# DDS_rev01.net
KiCad netlist of a schematic drawn in EAGLE
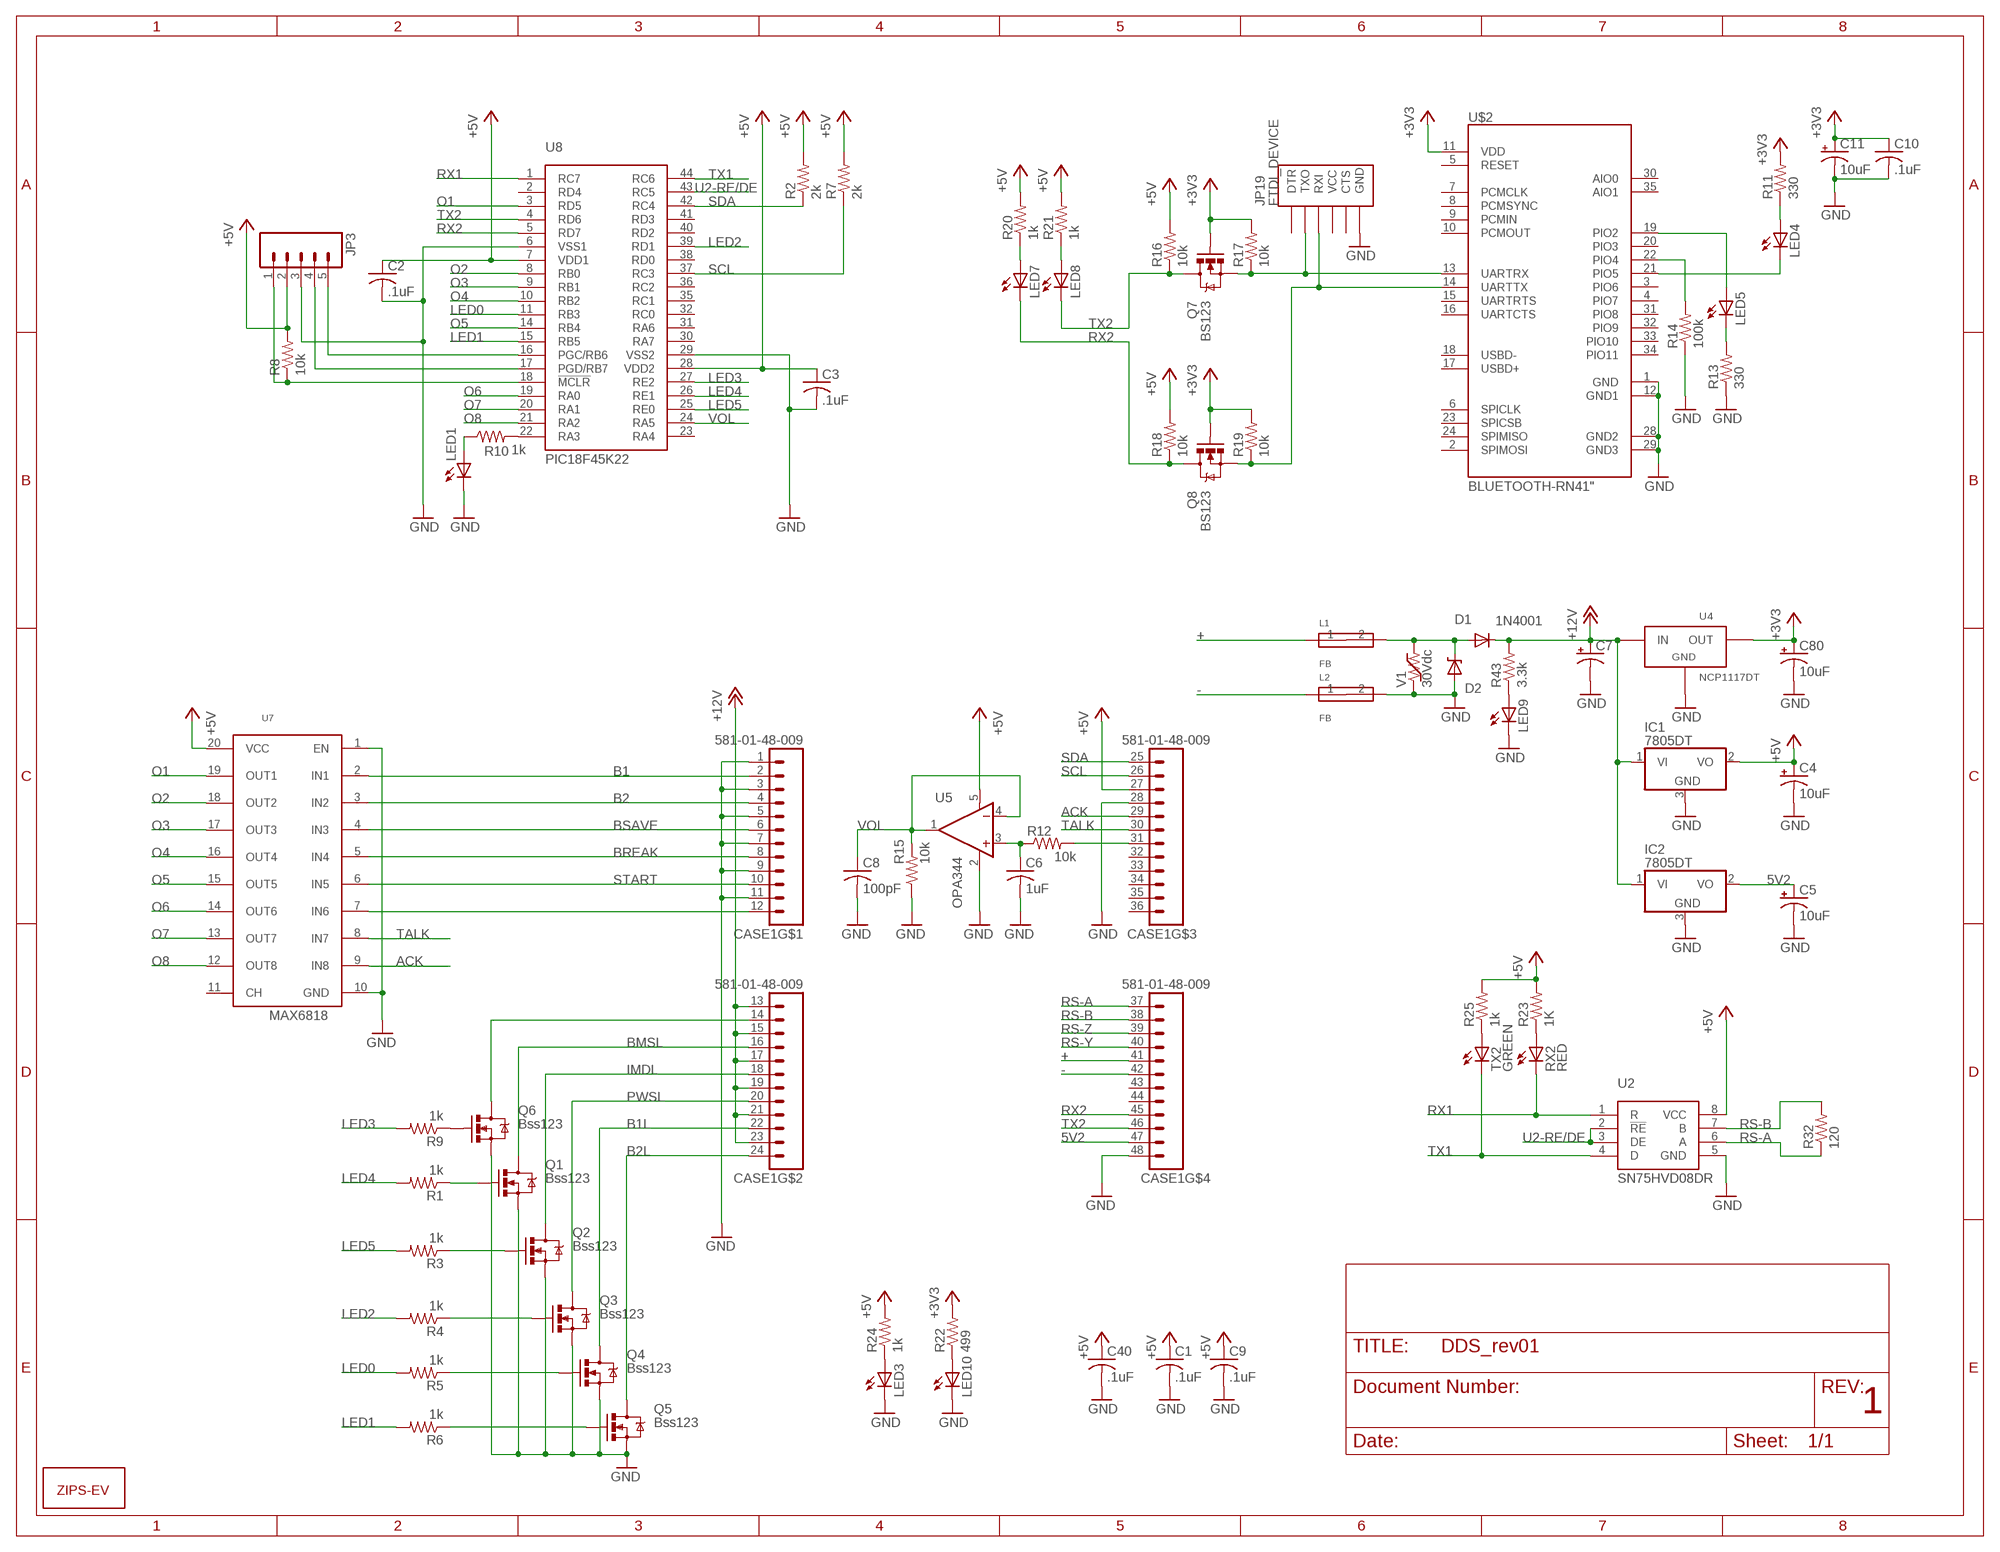
[diagram p0: schematic, sheet 1]

(export (version "E")
  (design (tool "Eeschema 10.0.6"))
  (components
    (comp (ref "C1")
      (value ".1uF")
      (footprint "eagle-import:C0805")
      (libsource (lib "eagle-import") (part "C-USC0805"))
    )
    (comp (ref "C2")
      (value ".1uF")
      (footprint "eagle-import:C0805")
      (libsource (lib "eagle-import") (part "C-USC0805"))
    )
    (comp (ref "C3")
      (value ".1uF")
      (footprint "eagle-import:C0805")
      (libsource (lib "eagle-import") (part "C-USC0805"))
    )
    (comp (ref "C4")
      (value "10uF")
      (footprint "eagle-import:POLC1206")
      (libsource (lib "eagle-import") (part "POLCAP"))
    )
    (comp (ref "C5")
      (value "10uF")
      (footprint "eagle-import:POLC1206")
      (libsource (lib "eagle-import") (part "POLCAP"))
    )
    (comp (ref "C6")
      (value "1uF")
      (footprint "eagle-import:C0805")
      (libsource (lib "eagle-import") (part "C-USC0805"))
    )
    (comp (ref "C7")
      (value "CAP_POL7343")
      (footprint "eagle-import:EIA7343")
      (libsource (lib "eagle-import") (part "CAP_POL7343"))
    )
    (comp (ref "C8")
      (value "100pF")
      (footprint "eagle-import:C0805")
      (libsource (lib "eagle-import") (part "C-USC0805"))
    )
    (comp (ref "C9")
      (value ".1uF")
      (footprint "eagle-import:C0805")
      (libsource (lib "eagle-import") (part "C-USC0805"))
    )
    (comp (ref "C10")
      (value ".1uF")
      (footprint "eagle-import:C0805")
      (libsource (lib "eagle-import") (part "C-USC0805"))
    )
    (comp (ref "C11")
      (value "10uF")
      (footprint "eagle-import:POLC1206")
      (libsource (lib "eagle-import") (part "POLCAP"))
    )
    (comp (ref "C40")
      (value ".1uF")
      (footprint "eagle-import:C0805")
      (libsource (lib "eagle-import") (part "C-USC0805"))
    )
    (comp (ref "C80")
      (value "10uF")
      (footprint "eagle-import:POLC1206")
      (libsource (lib "eagle-import") (part "POLCAP"))
    )
    (comp (ref "CASE1")
      (value "581-01-48-009")
      (footprint "eagle-import:581-01-48-009")
      (libsource (lib "eagle-import") (part "581-01-48-009"))
    )
    (comp (ref "D1")
      (value "1N4001")
      (footprint "eagle-import:SOD123")
      (libsource (lib "eagle-import") (part "DIODE-SOD123"))
    )
    (comp (ref "D2")
      (value "MM5Z30")
      (footprint "eagle-import:SOD-523F")
      (libsource (lib "eagle-import") (part "MM5Z30"))
    )
    (comp (ref "IC1")
      (value "7805DT")
      (footprint "eagle-import:TO252")
      (libsource (lib "eagle-import") (part "78DT05"))
    )
    (comp (ref "IC2")
      (value "7805DT")
      (footprint "eagle-import:TO252")
      (libsource (lib "eagle-import") (part "78DT05"))
    )
    (comp (ref "JP3")
      (value "M05LOCK_LONGPADS")
      (footprint "eagle-import:1X05_LOCK_LONGPADS")
      (libsource (lib "eagle-import") (part "M05LOCK_LONGPADS"))
    )
    (comp (ref "JP19")
      (value "FTDI_DEVICE")
      (footprint "eagle-import:FTDI_DEVICE_SIDE")
      (libsource (lib "eagle-import") (part "FTDI_DEVICE"))
    )
    (comp (ref "L1")
      (value "FB")
      (footprint "eagle-import:0603")
      (libsource (lib "eagle-import") (part "FERITEBEAD"))
    )
    (comp (ref "L2")
      (value "FB")
      (footprint "eagle-import:0603")
      (libsource (lib "eagle-import") (part "FERITEBEAD"))
    )
    (comp (ref "LED1")
      (value "LEDCHIP-LED0805")
      (footprint "eagle-import:CHIP-LED0805")
      (libsource (lib "eagle-import") (part "LEDCHIP-LED0805"))
    )
    (comp (ref "LED3")
      (value "LEDCHIP-LED0805")
      (footprint "eagle-import:CHIP-LED0805")
      (libsource (lib "eagle-import") (part "LEDCHIP-LED0805"))
    )
    (comp (ref "LED4")
      (value "LEDCHIP-LED0805")
      (footprint "eagle-import:CHIP-LED0805")
      (libsource (lib "eagle-import") (part "led_LEDCHIP-LED0805"))
    )
    (comp (ref "LED5")
      (value "LEDCHIP-LED0805")
      (footprint "eagle-import:CHIP-LED0805")
      (libsource (lib "eagle-import") (part "led_LEDCHIP-LED0805"))
    )
    (comp (ref "LED7")
      (value "LEDCHIP-LED0805")
      (footprint "eagle-import:CHIP-LED0805")
      (libsource (lib "eagle-import") (part "led_LEDCHIP-LED0805"))
    )
    (comp (ref "LED8")
      (value "LEDCHIP-LED0805")
      (footprint "eagle-import:CHIP-LED0805")
      (libsource (lib "eagle-import") (part "led_LEDCHIP-LED0805"))
    )
    (comp (ref "LED9")
      (value "LEDCHIP-LED0805")
      (footprint "eagle-import:CHIP-LED0805")
      (libsource (lib "eagle-import") (part "LEDCHIP-LED0805"))
    )
    (comp (ref "LED10")
      (value "LEDCHIP-LED0805")
      (footprint "eagle-import:CHIP-LED0805")
      (libsource (lib "eagle-import") (part "LEDCHIP-LED0805"))
    )
    (comp (ref "Q1")
      (value "Bss123")
      (footprint "eagle-import:SOT23")
      (libsource (lib "eagle-import") (part "MOSFET-NCHANNELBSS123LT1G"))
    )
    (comp (ref "Q2")
      (value "Bss123")
      (footprint "eagle-import:SOT23")
      (libsource (lib "eagle-import") (part "MOSFET-NCHANNELBSS123LT1G"))
    )
    (comp (ref "Q3")
      (value "Bss123")
      (footprint "eagle-import:SOT23")
      (libsource (lib "eagle-import") (part "MOSFET-NCHANNELBSS123LT1G"))
    )
    (comp (ref "Q4")
      (value "Bss123")
      (footprint "eagle-import:SOT23")
      (libsource (lib "eagle-import") (part "MOSFET-NCHANNELBSS123LT1G"))
    )
    (comp (ref "Q5")
      (value "Bss123")
      (footprint "eagle-import:SOT23")
      (libsource (lib "eagle-import") (part "MOSFET-NCHANNELBSS123LT1G"))
    )
    (comp (ref "Q6")
      (value "Bss123")
      (footprint "eagle-import:SOT23")
      (libsource (lib "eagle-import") (part "MOSFET-NCHANNELBSS123LT1G"))
    )
    (comp (ref "Q7")
      (value "BS123")
      (footprint "eagle-import:SOT23")
      (libsource (lib "eagle-import") (part "MOSFET-NCHANNELBSS123LT1G"))
    )
    (comp (ref "Q8")
      (value "BS123")
      (footprint "eagle-import:SOT23")
      (libsource (lib "eagle-import") (part "MOSFET-NCHANNELBSS123LT1G"))
    )
    (comp (ref "R1")
      (value "1k")
      (footprint "eagle-import:R0805")
      (libsource (lib "eagle-import") (part "R-US_R0805"))
    )
    (comp (ref "R2")
      (value "2k")
      (footprint "eagle-import:R0805")
      (libsource (lib "eagle-import") (part "R-US_R0805"))
    )
    (comp (ref "R3")
      (value "1k")
      (footprint "eagle-import:R0805")
      (libsource (lib "eagle-import") (part "R-US_R0805"))
    )
    (comp (ref "R4")
      (value "1k")
      (footprint "eagle-import:R0805")
      (libsource (lib "eagle-import") (part "R-US_R0805"))
    )
    (comp (ref "R5")
      (value "1k")
      (footprint "eagle-import:R0805")
      (libsource (lib "eagle-import") (part "R-US_R0805"))
    )
    (comp (ref "R6")
      (value "1k")
      (footprint "eagle-import:R0805")
      (libsource (lib "eagle-import") (part "R-US_R0805"))
    )
    (comp (ref "R7")
      (value "2k")
      (footprint "eagle-import:R0805")
      (libsource (lib "eagle-import") (part "R-US_R0805"))
    )
    (comp (ref "R8")
      (value "10k")
      (footprint "eagle-import:0805")
      (libsource (lib "eagle-import") (part "RESISTOR0805-RES"))
    )
    (comp (ref "R9")
      (value "1k")
      (footprint "eagle-import:R0805")
      (libsource (lib "eagle-import") (part "R-US_R0805"))
    )
    (comp (ref "R10")
      (value "1k")
      (footprint "eagle-import:R0805")
      (libsource (lib "eagle-import") (part "R-US_R0805"))
    )
    (comp (ref "R11")
      (value "330")
      (footprint "eagle-import:0805")
      (libsource (lib "eagle-import") (part "RESISTOR0805-RES"))
    )
    (comp (ref "R12")
      (value "10k")
      (footprint "eagle-import:R0805")
      (libsource (lib "eagle-import") (part "R-US_R0805"))
    )
    (comp (ref "R13")
      (value "330")
      (footprint "eagle-import:0805")
      (libsource (lib "eagle-import") (part "RESISTOR0805-RES"))
    )
    (comp (ref "R14")
      (value "100k")
      (footprint "eagle-import:0805")
      (libsource (lib "eagle-import") (part "RESISTOR0805-RES"))
    )
    (comp (ref "R15")
      (value "10k")
      (footprint "eagle-import:R0805")
      (libsource (lib "eagle-import") (part "R-US_R0805"))
    )
    (comp (ref "R16")
      (value "10k")
      (footprint "eagle-import:0805")
      (libsource (lib "eagle-import") (part "RESISTOR0805-RES"))
    )
    (comp (ref "R17")
      (value "10k")
      (footprint "eagle-import:0805")
      (libsource (lib "eagle-import") (part "RESISTOR0805-RES"))
    )
    (comp (ref "R18")
      (value "10k")
      (footprint "eagle-import:0805")
      (libsource (lib "eagle-import") (part "RESISTOR0805-RES"))
    )
    (comp (ref "R19")
      (value "10k")
      (footprint "eagle-import:0805")
      (libsource (lib "eagle-import") (part "RESISTOR0805-RES"))
    )
    (comp (ref "R20")
      (value "1k")
      (footprint "eagle-import:0805")
      (libsource (lib "eagle-import") (part "RESISTOR0805-RES"))
    )
    (comp (ref "R21")
      (value "1k")
      (footprint "eagle-import:0805")
      (libsource (lib "eagle-import") (part "RESISTOR0805-RES"))
    )
    (comp (ref "R22")
      (value "499")
      (footprint "eagle-import:R0805")
      (libsource (lib "eagle-import") (part "R-US_R0805"))
    )
    (comp (ref "R23")
      (value "1K")
      (footprint "eagle-import:R0805")
      (libsource (lib "eagle-import") (part "R-US_R0805"))
    )
    (comp (ref "R24")
      (value "1k")
      (footprint "eagle-import:R0805")
      (libsource (lib "eagle-import") (part "R-US_R0805"))
    )
    (comp (ref "R25")
      (value "1k")
      (footprint "eagle-import:R0805")
      (libsource (lib "eagle-import") (part "R-US_R0805"))
    )
    (comp (ref "R32")
      (value "120")
      (footprint "eagle-import:R0805")
      (libsource (lib "eagle-import") (part "R-US_R0805"))
    )
    (comp (ref "R43")
      (value "3.3k")
      (footprint "eagle-import:R0805")
      (libsource (lib "eagle-import") (part "R-US_R0805"))
    )
    (comp (ref "RX2")
      (value "RED")
      (footprint "eagle-import:CHIPLED_0805")
      (libsource (lib "eagle-import") (part "LEDCHIPLED_0805"))
    )
    (comp (ref "TX2")
      (value "GREEN")
      (footprint "eagle-import:CHIPLED_0805")
      (libsource (lib "eagle-import") (part "LEDCHIPLED_0805"))
    )
    (comp (ref "U$1")
      (value "LOGO")
      (footprint "eagle-import:L-L")
      (libsource (lib "eagle-import") (part "LOGO"))
    )
    (comp (ref "U$2")
      (value "BLUETOOTH-RN41\"")
      (footprint "eagle-import:RN41")
      (libsource (lib "eagle-import") (part "BLUETOOTH-RN41{dblquote}"))
    )
    (comp (ref "U2")
      (value "SN75HVD08DR")
      (footprint "eagle-import:SO-8")
      (libsource (lib "eagle-import") (part "SN75HVD08DR"))
    )
    (comp (ref "U4")
      (value "NCP1117DT")
      (footprint "eagle-import:DPAK")
      (libsource (lib "eagle-import") (part "NCP1117DT"))
    )
    (comp (ref "U5")
      (value "OPA344")
      (footprint "eagle-import:SOT23-5")
      (libsource (lib "eagle-import") (part "OPA344"))
    )
    (comp (ref "U7")
      (value "MAX6818")
      (footprint "eagle-import:SSOP-20")
      (libsource (lib "eagle-import") (part "MAX6818"))
    )
    (comp (ref "U8")
      (value "PIC18F45K22")
      (footprint "eagle-import:TQFP-44")
      (libsource (lib "eagle-import") (part "PIC18F45K22"))
    )
    (comp (ref "V1")
      (value "30Vdc")
      (footprint "eagle-import:0603")
      (libsource (lib "eagle-import") (part "VAR-RES"))
    )
  )
  (nets
    (net (code "1") (name "+3V3") (class "Default")
      (node (ref "C10") (pin "1") (pinfunction "1_1") (pintype "passive"))
      (node (ref "C11") (pin "1") (pinfunction "+_1") (pintype "passive"))
      (node (ref "C80") (pin "1") (pinfunction "+_1") (pintype "passive"))
      (node (ref "Q7") (pin "1") (pinfunction "G_1") (pintype "passive"))
      (node (ref "Q8") (pin "1") (pinfunction "G_1") (pintype "passive"))
      (node (ref "R11") (pin "2") (pinfunction "2_2") (pintype "passive"))
      (node (ref "R17") (pin "2") (pinfunction "2_2") (pintype "passive"))
      (node (ref "R19") (pin "2") (pinfunction "2_2") (pintype "passive"))
      (node (ref "R22") (pin "2") (pinfunction "2_2") (pintype "passive"))
      (node (ref "U$2") (pin "11") (pinfunction "VDD_11") (pintype "bidirectional"))
      (node (ref "U4") (pin "2") (pinfunction "OUT_2") (pintype "bidirectional"))
    )
    (net (code "2") (name "+5V") (class "Default")
      (node (ref "C1") (pin "1") (pinfunction "1_1") (pintype "passive"))
      (node (ref "C2") (pin "1") (pinfunction "1_1") (pintype "passive"))
      (node (ref "C3") (pin "1") (pinfunction "1_1") (pintype "passive"))
      (node (ref "C4") (pin "1") (pinfunction "+_1") (pintype "passive"))
      (node (ref "C40") (pin "1") (pinfunction "1_1") (pintype "passive"))
      (node (ref "C9") (pin "1") (pinfunction "1_1") (pintype "passive"))
      (node (ref "CASE1") (pin "27") (pinfunction "3_27") (pintype "passive"))
      (node (ref "IC1") (pin "2") (pinfunction "VO_2") (pintype "passive"))
      (node (ref "JP3") (pin "2") (pinfunction "2_2") (pintype "passive"))
      (node (ref "R16") (pin "2") (pinfunction "2_2") (pintype "passive"))
      (node (ref "R18") (pin "2") (pinfunction "2_2") (pintype "passive"))
      (node (ref "R2") (pin "2") (pinfunction "2_2") (pintype "passive"))
      (node (ref "R20") (pin "2") (pinfunction "2_2") (pintype "passive"))
      (node (ref "R21") (pin "2") (pinfunction "2_2") (pintype "passive"))
      (node (ref "R23") (pin "2") (pinfunction "2_2") (pintype "passive"))
      (node (ref "R24") (pin "2") (pinfunction "2_2") (pintype "passive"))
      (node (ref "R25") (pin "2") (pinfunction "2_2") (pintype "passive"))
      (node (ref "R7") (pin "2") (pinfunction "2_2") (pintype "passive"))
      (node (ref "R8") (pin "2") (pinfunction "2_2") (pintype "passive"))
      (node (ref "U2") (pin "8") (pinfunction "VCC_8") (pintype "bidirectional"))
      (node (ref "U5") (pin "5") (pinfunction "V+_5") (pintype "power_in"))
      (node (ref "U7") (pin "20") (pinfunction "VCC_20") (pintype "bidirectional"))
      (node (ref "U8") (pin "28") (pinfunction "VDD2_28") (pintype "bidirectional"))
      (node (ref "U8") (pin "7") (pinfunction "VDD1_7") (pintype "bidirectional"))
    )
    (net (code "3") (name "+12V") (class "Default")
      (node (ref "C7") (pin "A") (pinfunction "+_A") (pintype "passive"))
      (node (ref "CASE1") (pin "13") (pinfunction "1_13") (pintype "passive"))
      (node (ref "CASE1") (pin "15") (pinfunction "3_15") (pintype "passive"))
      (node (ref "CASE1") (pin "17") (pinfunction "5_17") (pintype "passive"))
      (node (ref "CASE1") (pin "19") (pinfunction "7_19") (pintype "passive"))
      (node (ref "CASE1") (pin "21") (pinfunction "9_21") (pintype "passive"))
      (node (ref "CASE1") (pin "23") (pinfunction "11_23") (pintype "passive"))
      (node (ref "D1") (pin "C") (pinfunction "C_C") (pintype "passive"))
      (node (ref "IC1") (pin "1") (pinfunction "VI_1") (pintype "input"))
      (node (ref "IC2") (pin "1") (pinfunction "VI_1") (pintype "input"))
      (node (ref "R43") (pin "2") (pinfunction "2_2") (pintype "passive"))
      (node (ref "U4") (pin "3") (pinfunction "IN_3") (pintype "bidirectional"))
    )
    (net (code "4") (name "/+") (class "Default")
      (node (ref "CASE1") (pin "41") (pinfunction "5_41") (pintype "passive"))
      (node (ref "L1") (pin "1") (pinfunction "P$1_1") (pintype "bidirectional"))
    )
    (net (code "5") (name "/-") (class "Default")
      (node (ref "CASE1") (pin "42") (pinfunction "6_42") (pintype "passive"))
      (node (ref "L2") (pin "1") (pinfunction "P$1_1") (pintype "bidirectional"))
    )
    (net (code "6") (name "/5V2") (class "Default")
      (node (ref "C5") (pin "1") (pinfunction "+_1") (pintype "passive"))
      (node (ref "CASE1") (pin "47") (pinfunction "11_47") (pintype "passive"))
      (node (ref "IC2") (pin "2") (pinfunction "VO_2") (pintype "passive"))
    )
    (net (code "7") (name "/ACK") (class "Default")
      (node (ref "CASE1") (pin "29") (pinfunction "5_29") (pintype "passive"))
      (node (ref "U7") (pin "9") (pinfunction "IN8_9") (pintype "bidirectional"))
    )
    (net (code "8") (name "/B1") (class "Default")
      (node (ref "CASE1") (pin "2") (pinfunction "2_2") (pintype "passive"))
      (node (ref "U7") (pin "2") (pinfunction "IN1_2") (pintype "bidirectional"))
    )
    (net (code "9") (name "/B1L") (class "Default")
      (node (ref "CASE1") (pin "22") (pinfunction "10_22") (pintype "passive"))
      (node (ref "Q4") (pin "3") (pinfunction "D_3") (pintype "passive"))
    )
    (net (code "10") (name "/B2") (class "Default")
      (node (ref "CASE1") (pin "4") (pinfunction "4_4") (pintype "passive"))
      (node (ref "U7") (pin "3") (pinfunction "IN2_3") (pintype "bidirectional"))
    )
    (net (code "11") (name "/B2L") (class "Default")
      (node (ref "CASE1") (pin "24") (pinfunction "12_24") (pintype "passive"))
      (node (ref "Q5") (pin "3") (pinfunction "D_3") (pintype "passive"))
    )
    (net (code "12") (name "/BMSL") (class "Default")
      (node (ref "CASE1") (pin "16") (pinfunction "4_16") (pintype "passive"))
      (node (ref "Q1") (pin "3") (pinfunction "D_3") (pintype "passive"))
    )
    (net (code "13") (name "/BREAK") (class "Default")
      (node (ref "CASE1") (pin "8") (pinfunction "8_8") (pintype "passive"))
      (node (ref "U7") (pin "5") (pinfunction "IN4_5") (pintype "bidirectional"))
    )
    (net (code "14") (name "/BSAVE") (class "Default")
      (node (ref "CASE1") (pin "6") (pinfunction "6_6") (pintype "passive"))
      (node (ref "U7") (pin "4") (pinfunction "IN3_4") (pintype "bidirectional"))
    )
    (net (code "15") (name "/IMDL") (class "Default")
      (node (ref "CASE1") (pin "18") (pinfunction "6_18") (pintype "passive"))
      (node (ref "Q2") (pin "3") (pinfunction "D_3") (pintype "passive"))
    )
    (net (code "16") (name "/LED0") (class "Default")
      (node (ref "R5") (pin "2") (pinfunction "2_2") (pintype "passive"))
      (node (ref "U8") (pin "11") (pinfunction "RB3_11") (pintype "bidirectional"))
    )
    (net (code "17") (name "/LED1") (class "Default")
      (node (ref "R6") (pin "2") (pinfunction "2_2") (pintype "passive"))
      (node (ref "U8") (pin "15") (pinfunction "RB5_15") (pintype "bidirectional"))
    )
    (net (code "18") (name "/LED2") (class "Default")
      (node (ref "R4") (pin "2") (pinfunction "2_2") (pintype "passive"))
      (node (ref "U8") (pin "39") (pinfunction "RD1_39") (pintype "bidirectional"))
    )
    (net (code "19") (name "/LED3") (class "Default")
      (node (ref "R9") (pin "2") (pinfunction "2_2") (pintype "passive"))
      (node (ref "U8") (pin "27") (pinfunction "RE2_27") (pintype "bidirectional"))
    )
    (net (code "20") (name "/LED4") (class "Default")
      (node (ref "R1") (pin "2") (pinfunction "2_2") (pintype "passive"))
      (node (ref "U8") (pin "26") (pinfunction "RE1_26") (pintype "bidirectional"))
    )
    (net (code "21") (name "/LED5") (class "Default")
      (node (ref "R3") (pin "2") (pinfunction "2_2") (pintype "passive"))
      (node (ref "U8") (pin "25") (pinfunction "RE0_25") (pintype "bidirectional"))
    )
    (net (code "22") (name "/O1") (class "Default")
      (node (ref "U7") (pin "19") (pinfunction "OUT1_19") (pintype "bidirectional"))
      (node (ref "U8") (pin "3") (pinfunction "RD5_3") (pintype "bidirectional"))
    )
    (net (code "23") (name "/O2") (class "Default")
      (node (ref "U7") (pin "18") (pinfunction "OUT2_18") (pintype "bidirectional"))
      (node (ref "U8") (pin "8") (pinfunction "RB0_8") (pintype "bidirectional"))
    )
    (net (code "24") (name "/O3") (class "Default")
      (node (ref "U7") (pin "17") (pinfunction "OUT3_17") (pintype "bidirectional"))
      (node (ref "U8") (pin "9") (pinfunction "RB1_9") (pintype "bidirectional"))
    )
    (net (code "25") (name "/O4") (class "Default")
      (node (ref "U7") (pin "16") (pinfunction "OUT4_16") (pintype "bidirectional"))
      (node (ref "U8") (pin "10") (pinfunction "RB2_10") (pintype "bidirectional"))
    )
    (net (code "26") (name "/O5") (class "Default")
      (node (ref "U7") (pin "15") (pinfunction "OUT5_15") (pintype "bidirectional"))
      (node (ref "U8") (pin "14") (pinfunction "RB4_14") (pintype "bidirectional"))
    )
    (net (code "27") (name "/O6") (class "Default")
      (node (ref "U7") (pin "14") (pinfunction "OUT6_14") (pintype "bidirectional"))
      (node (ref "U8") (pin "19") (pinfunction "RA0_19") (pintype "bidirectional"))
    )
    (net (code "28") (name "/O7") (class "Default")
      (node (ref "U7") (pin "13") (pinfunction "OUT7_13") (pintype "bidirectional"))
      (node (ref "U8") (pin "20") (pinfunction "RA1_20") (pintype "bidirectional"))
    )
    (net (code "29") (name "/O8") (class "Default")
      (node (ref "U7") (pin "12") (pinfunction "OUT8_12") (pintype "bidirectional"))
      (node (ref "U8") (pin "21") (pinfunction "RA2_21") (pintype "bidirectional"))
    )
    (net (code "30") (name "/PWSL") (class "Default")
      (node (ref "CASE1") (pin "20") (pinfunction "8_20") (pintype "passive"))
      (node (ref "Q3") (pin "3") (pinfunction "D_3") (pintype "passive"))
    )
    (net (code "31") (name "/RS-A") (class "Default")
      (node (ref "CASE1") (pin "37") (pinfunction "1_37") (pintype "passive"))
      (node (ref "R32") (pin "1") (pinfunction "1_1") (pintype "passive"))
      (node (ref "U2") (pin "6") (pinfunction "A_6") (pintype "bidirectional"))
    )
    (net (code "32") (name "/RS-B") (class "Default")
      (node (ref "CASE1") (pin "38") (pinfunction "2_38") (pintype "passive"))
      (node (ref "R32") (pin "2") (pinfunction "2_2") (pintype "passive"))
      (node (ref "U2") (pin "7") (pinfunction "B_7") (pintype "bidirectional"))
    )
    (net (code "33") (name "/RS-Y") (class "Default")
      (node (ref "CASE1") (pin "40") (pinfunction "4_40") (pintype "passive"))
    )
    (net (code "34") (name "/RS-Z") (class "Default")
      (node (ref "CASE1") (pin "39") (pinfunction "3_39") (pintype "passive"))
    )
    (net (code "35") (name "/RX1") (class "Default")
      (node (ref "RX2") (pin "C") (pinfunction "C_C") (pintype "passive"))
      (node (ref "U2") (pin "1") (pinfunction "R_1") (pintype "bidirectional"))
      (node (ref "U8") (pin "1") (pinfunction "RC7_1") (pintype "bidirectional"))
    )
    (net (code "36") (name "/RX2") (class "Default")
      (node (ref "CASE1") (pin "45") (pinfunction "9_45") (pintype "passive"))
      (node (ref "LED7") (pin "C") (pinfunction "C_C") (pintype "passive"))
      (node (ref "Q8") (pin "3") (pinfunction "D_3") (pintype "passive"))
      (node (ref "R18") (pin "1") (pinfunction "1_1") (pintype "passive"))
      (node (ref "U8") (pin "5") (pinfunction "RD7_5") (pintype "bidirectional"))
    )
    (net (code "37") (name "/SCL") (class "Default")
      (node (ref "CASE1") (pin "26") (pinfunction "2_26") (pintype "passive"))
      (node (ref "R7") (pin "1") (pinfunction "1_1") (pintype "passive"))
      (node (ref "U8") (pin "37") (pinfunction "RC3_37") (pintype "bidirectional"))
    )
    (net (code "38") (name "/SDA") (class "Default")
      (node (ref "CASE1") (pin "25") (pinfunction "1_25") (pintype "passive"))
      (node (ref "R2") (pin "1") (pinfunction "1_1") (pintype "passive"))
      (node (ref "U8") (pin "42") (pinfunction "RC4_42") (pintype "bidirectional"))
    )
    (net (code "39") (name "/START") (class "Default")
      (node (ref "CASE1") (pin "10") (pinfunction "10_10") (pintype "passive"))
      (node (ref "U7") (pin "6") (pinfunction "IN5_6") (pintype "bidirectional"))
    )
    (net (code "40") (name "/TALK") (class "Default")
      (node (ref "CASE1") (pin "30") (pinfunction "6_30") (pintype "passive"))
      (node (ref "U7") (pin "8") (pinfunction "IN7_8") (pintype "bidirectional"))
    )
    (net (code "41") (name "/TX1") (class "Default")
      (node (ref "TX2") (pin "C") (pinfunction "C_C") (pintype "passive"))
      (node (ref "U2") (pin "4") (pinfunction "D_4") (pintype "bidirectional"))
      (node (ref "U8") (pin "44") (pinfunction "RC6_44") (pintype "bidirectional"))
    )
    (net (code "42") (name "/TX2") (class "Default")
      (node (ref "CASE1") (pin "46") (pinfunction "10_46") (pintype "passive"))
      (node (ref "LED8") (pin "C") (pinfunction "C_C") (pintype "passive"))
      (node (ref "Q7") (pin "3") (pinfunction "D_3") (pintype "passive"))
      (node (ref "R16") (pin "1") (pinfunction "1_1") (pintype "passive"))
      (node (ref "U8") (pin "4") (pinfunction "RD6_4") (pintype "bidirectional"))
    )
    (net (code "43") (name "/U2-RE{slash}DE") (class "Default")
      (node (ref "U2") (pin "2") (pinfunction "~{RE}_2") (pintype "bidirectional"))
      (node (ref "U2") (pin "3") (pinfunction "DE_3") (pintype "bidirectional"))
      (node (ref "U8") (pin "43") (pinfunction "RC5_43") (pintype "bidirectional"))
    )
    (net (code "44") (name "/VOL") (class "Default")
      (node (ref "C8") (pin "1") (pinfunction "1_1") (pintype "passive"))
      (node (ref "R15") (pin "2") (pinfunction "2_2") (pintype "passive"))
      (node (ref "U5") (pin "1") (pinfunction "OUT_1") (pintype "output"))
      (node (ref "U5") (pin "4") (pinfunction "-IN_4") (pintype "input"))
      (node (ref "U8") (pin "24") (pinfunction "RA5_24") (pintype "bidirectional"))
    )
    (net (code "45") (name "GND") (class "Default")
      (node (ref "C1") (pin "2") (pinfunction "2_2") (pintype "passive"))
      (node (ref "C10") (pin "2") (pinfunction "2_2") (pintype "passive"))
      (node (ref "C11") (pin "2") (pinfunction "-_2") (pintype "passive"))
      (node (ref "C2") (pin "2") (pinfunction "2_2") (pintype "passive"))
      (node (ref "C3") (pin "2") (pinfunction "2_2") (pintype "passive"))
      (node (ref "C4") (pin "2") (pinfunction "-_2") (pintype "passive"))
      (node (ref "C40") (pin "2") (pinfunction "2_2") (pintype "passive"))
      (node (ref "C5") (pin "2") (pinfunction "-_2") (pintype "passive"))
      (node (ref "C6") (pin "2") (pinfunction "2_2") (pintype "passive"))
      (node (ref "C7") (pin "C") (pinfunction "-_C") (pintype "passive"))
      (node (ref "C8") (pin "2") (pinfunction "2_2") (pintype "passive"))
      (node (ref "C80") (pin "2") (pinfunction "-_2") (pintype "passive"))
      (node (ref "C9") (pin "2") (pinfunction "2_2") (pintype "passive"))
      (node (ref "CASE1") (pin "1") (pinfunction "1_1") (pintype "passive"))
      (node (ref "CASE1") (pin "11") (pinfunction "11_11") (pintype "passive"))
      (node (ref "CASE1") (pin "28") (pinfunction "4_28") (pintype "passive"))
      (node (ref "CASE1") (pin "3") (pinfunction "3_3") (pintype "passive"))
      (node (ref "CASE1") (pin "48") (pinfunction "12_48") (pintype "passive"))
      (node (ref "CASE1") (pin "5") (pinfunction "5_5") (pintype "passive"))
      (node (ref "CASE1") (pin "7") (pinfunction "7_7") (pintype "passive"))
      (node (ref "CASE1") (pin "9") (pinfunction "9_9") (pintype "passive"))
      (node (ref "D2") (pin "A") (pinfunction "A_A") (pintype "passive"))
      (node (ref "IC1") (pin "3") (pinfunction "GND_3") (pintype "passive"))
      (node (ref "IC2") (pin "3") (pinfunction "GND_3") (pintype "passive"))
      (node (ref "JP19") (pin "P$6") (pinfunction "GND_P$6") (pintype "bidirectional"))
      (node (ref "JP3") (pin "3") (pinfunction "3_3") (pintype "passive"))
      (node (ref "L2") (pin "2") (pinfunction "P$2_2") (pintype "bidirectional"))
      (node (ref "LED1") (pin "C") (pinfunction "C_C") (pintype "passive"))
      (node (ref "LED10") (pin "C") (pinfunction "C_C") (pintype "passive"))
      (node (ref "LED3") (pin "C") (pinfunction "C_C") (pintype "passive"))
      (node (ref "LED9") (pin "C") (pinfunction "C_C") (pintype "passive"))
      (node (ref "Q1") (pin "2") (pinfunction "S_2") (pintype "passive"))
      (node (ref "Q2") (pin "2") (pinfunction "S_2") (pintype "passive"))
      (node (ref "Q3") (pin "2") (pinfunction "S_2") (pintype "passive"))
      (node (ref "Q4") (pin "2") (pinfunction "S_2") (pintype "passive"))
      (node (ref "Q5") (pin "2") (pinfunction "S_2") (pintype "passive"))
      (node (ref "Q6") (pin "2") (pinfunction "S_2") (pintype "passive"))
      (node (ref "R13") (pin "1") (pinfunction "1_1") (pintype "passive"))
      (node (ref "R14") (pin "1") (pinfunction "1_1") (pintype "passive"))
      (node (ref "R15") (pin "1") (pinfunction "1_1") (pintype "passive"))
      (node (ref "U$2") (pin "1") (pinfunction "GND_1") (pintype "bidirectional"))
      (node (ref "U$2") (pin "12") (pinfunction "GND1_12") (pintype "bidirectional"))
      (node (ref "U$2") (pin "28") (pinfunction "GND2_28") (pintype "bidirectional"))
      (node (ref "U$2") (pin "29") (pinfunction "GND3_29") (pintype "bidirectional"))
      (node (ref "U2") (pin "5") (pinfunction "GND_5") (pintype "bidirectional"))
      (node (ref "U4") (pin "1") (pinfunction "GND_1") (pintype "bidirectional"))
      (node (ref "U5") (pin "2") (pinfunction "V-_2") (pintype "power_in"))
      (node (ref "U7") (pin "1") (pinfunction "EN_1") (pintype "bidirectional"))
      (node (ref "U7") (pin "10") (pinfunction "GND_10") (pintype "bidirectional"))
      (node (ref "U8") (pin "29") (pinfunction "VSS2_29") (pintype "bidirectional"))
      (node (ref "U8") (pin "6") (pinfunction "VSS1_6") (pintype "bidirectional"))
      (node (ref "V1") (pin "1") (pinfunction "1_1") (pintype "passive"))
    )
    (net (code "46") (name "Net-(CASE1B-2)") (class "Default")
      (node (ref "CASE1") (pin "14") (pinfunction "2_14") (pintype "passive"))
      (node (ref "Q6") (pin "3") (pinfunction "D_3") (pintype "passive"))
    )
    (net (code "47") (name "Net-(CASE1C-7)") (class "Default")
      (node (ref "CASE1") (pin "31") (pinfunction "7_31") (pintype "passive"))
      (node (ref "R12") (pin "2") (pinfunction "2_2") (pintype "passive"))
    )
    (net (code "48") (name "Net-(JP19-RXI)") (class "Default")
      (node (ref "JP19") (pin "P$3") (pinfunction "RXI_P$3") (pintype "bidirectional"))
      (node (ref "Q8") (pin "2") (pinfunction "S_2") (pintype "passive"))
      (node (ref "R19") (pin "1") (pinfunction "1_1") (pintype "passive"))
      (node (ref "U$2") (pin "14") (pinfunction "UARTTX_14") (pintype "bidirectional"))
    )
    (net (code "49") (name "Net-(JP19-TXO)") (class "Default")
      (node (ref "JP19") (pin "P$2") (pinfunction "TXO_P$2") (pintype "bidirectional"))
      (node (ref "Q7") (pin "2") (pinfunction "S_2") (pintype "passive"))
      (node (ref "R17") (pin "1") (pinfunction "1_1") (pintype "passive"))
      (node (ref "U$2") (pin "13") (pinfunction "UARTRX_13") (pintype "bidirectional"))
    )
    (net (code "50") (name "Net-(L1-P$2)") (class "Default")
      (node (ref "D1") (pin "A") (pinfunction "A_A") (pintype "passive"))
      (node (ref "D2") (pin "C") (pinfunction "C_C") (pintype "passive"))
      (node (ref "L1") (pin "2") (pinfunction "P$2_2") (pintype "bidirectional"))
      (node (ref "V1") (pin "2") (pinfunction "2_2") (pintype "passive"))
    )
    (net (code "51") (name "Net-(LED1-PadA)") (class "Default")
      (node (ref "LED1") (pin "A") (pinfunction "A_A") (pintype "passive"))
      (node (ref "R10") (pin "1") (pinfunction "1_1") (pintype "passive"))
    )
    (net (code "52") (name "Net-(LED3-PadA)") (class "Default")
      (node (ref "LED3") (pin "A") (pinfunction "A_A") (pintype "passive"))
      (node (ref "R24") (pin "1") (pinfunction "1_1") (pintype "passive"))
    )
    (net (code "53") (name "Net-(LED4-PadA)") (class "Default")
      (node (ref "LED4") (pin "A") (pinfunction "A_A") (pintype "passive"))
      (node (ref "R11") (pin "1") (pinfunction "1_1") (pintype "passive"))
    )
    (net (code "54") (name "Net-(LED5-PadC)") (class "Default")
      (node (ref "LED5") (pin "C") (pinfunction "C_C") (pintype "passive"))
      (node (ref "R13") (pin "2") (pinfunction "2_2") (pintype "passive"))
    )
    (net (code "55") (name "Net-(LED7-PadA)") (class "Default")
      (node (ref "LED7") (pin "A") (pinfunction "A_A") (pintype "passive"))
      (node (ref "R20") (pin "1") (pinfunction "1_1") (pintype "passive"))
    )
    (net (code "56") (name "Net-(LED8-PadA)") (class "Default")
      (node (ref "LED8") (pin "A") (pinfunction "A_A") (pintype "passive"))
      (node (ref "R21") (pin "1") (pinfunction "1_1") (pintype "passive"))
    )
    (net (code "57") (name "Net-(LED9-PadA)") (class "Default")
      (node (ref "LED9") (pin "A") (pinfunction "A_A") (pintype "passive"))
      (node (ref "R43") (pin "1") (pinfunction "1_1") (pintype "passive"))
    )
    (net (code "58") (name "Net-(LED10-PadA)") (class "Default")
      (node (ref "LED10") (pin "A") (pinfunction "A_A") (pintype "passive"))
      (node (ref "R22") (pin "1") (pinfunction "1_1") (pintype "passive"))
    )
    (net (code "59") (name "Net-(Q1-G)") (class "Default")
      (node (ref "Q1") (pin "1") (pinfunction "G_1") (pintype "passive"))
      (node (ref "R1") (pin "1") (pinfunction "1_1") (pintype "passive"))
    )
    (net (code "60") (name "Net-(Q2-G)") (class "Default")
      (node (ref "Q2") (pin "1") (pinfunction "G_1") (pintype "passive"))
      (node (ref "R3") (pin "1") (pinfunction "1_1") (pintype "passive"))
    )
    (net (code "61") (name "Net-(Q3-G)") (class "Default")
      (node (ref "Q3") (pin "1") (pinfunction "G_1") (pintype "passive"))
      (node (ref "R4") (pin "1") (pinfunction "1_1") (pintype "passive"))
    )
    (net (code "62") (name "Net-(Q4-G)") (class "Default")
      (node (ref "Q4") (pin "1") (pinfunction "G_1") (pintype "passive"))
      (node (ref "R5") (pin "1") (pinfunction "1_1") (pintype "passive"))
    )
    (net (code "63") (name "Net-(Q5-G)") (class "Default")
      (node (ref "Q5") (pin "1") (pinfunction "G_1") (pintype "passive"))
      (node (ref "R6") (pin "1") (pinfunction "1_1") (pintype "passive"))
    )
    (net (code "64") (name "Net-(Q6-G)") (class "Default")
      (node (ref "Q6") (pin "1") (pinfunction "G_1") (pintype "passive"))
      (node (ref "R9") (pin "1") (pinfunction "1_1") (pintype "passive"))
    )
    (net (code "65") (name "Net-(R23-Pad1)") (class "Default")
      (node (ref "R23") (pin "1") (pinfunction "1_1") (pintype "passive"))
      (node (ref "RX2") (pin "A") (pinfunction "A_A") (pintype "passive"))
    )
    (net (code "66") (name "Net-(R25-Pad1)") (class "Default")
      (node (ref "R25") (pin "1") (pinfunction "1_1") (pintype "passive"))
      (node (ref "TX2") (pin "A") (pinfunction "A_A") (pintype "passive"))
    )
    (net (code "67") (name "Net-(U$2-PIO2)") (class "Default")
      (node (ref "LED5") (pin "A") (pinfunction "A_A") (pintype "passive"))
      (node (ref "U$2") (pin "19") (pinfunction "PIO2_19") (pintype "bidirectional"))
    )
    (net (code "68") (name "Net-(U$2-PIO4)") (class "Default")
      (node (ref "R14") (pin "2") (pinfunction "2_2") (pintype "passive"))
      (node (ref "U$2") (pin "22") (pinfunction "PIO4_22") (pintype "bidirectional"))
    )
    (net (code "69") (name "Net-(U$2-PIO5)") (class "Default")
      (node (ref "LED4") (pin "C") (pinfunction "C_C") (pintype "passive"))
      (node (ref "U$2") (pin "21") (pinfunction "PIO5_21") (pintype "bidirectional"))
    )
    (net (code "70") (name "Net-(U5-+IN)") (class "Default")
      (node (ref "C6") (pin "1") (pinfunction "1_1") (pintype "passive"))
      (node (ref "R12") (pin "1") (pinfunction "1_1") (pintype "passive"))
      (node (ref "U5") (pin "3") (pinfunction "+IN_3") (pintype "input"))
    )
    (net (code "71") (name "Net-(U7-IN6)") (class "Default")
      (node (ref "CASE1") (pin "12") (pinfunction "12_12") (pintype "passive"))
      (node (ref "U7") (pin "7") (pinfunction "IN6_7") (pintype "bidirectional"))
    )
    (net (code "72") (name "Net-(U8-PGC{slash}RB6)") (class "Default")
      (node (ref "JP3") (pin "5") (pinfunction "5_5") (pintype "passive"))
      (node (ref "U8") (pin "16") (pinfunction "PGC/RB6_16") (pintype "bidirectional"))
    )
    (net (code "73") (name "Net-(U8-PGD{slash}RB7)") (class "Default")
      (node (ref "JP3") (pin "4") (pinfunction "4_4") (pintype "passive"))
      (node (ref "U8") (pin "17") (pinfunction "PGD/RB7_17") (pintype "bidirectional"))
    )
    (net (code "74") (name "Net-(U8-RA3)") (class "Default")
      (node (ref "R10") (pin "2") (pinfunction "2_2") (pintype "passive"))
      (node (ref "U8") (pin "22") (pinfunction "RA3_22") (pintype "bidirectional"))
    )
    (net (code "75") (name "Net-(U8-~{MCLR})") (class "Default")
      (node (ref "JP3") (pin "1") (pinfunction "1_1") (pintype "passive"))
      (node (ref "R8") (pin "1") (pinfunction "1_1") (pintype "passive"))
      (node (ref "U8") (pin "18") (pinfunction "~{MCLR}_18") (pintype "bidirectional"))
    )
    (net (code "76") (name "unconnected-(CASE1C-8-Pad32)") (class "Default")
      (node (ref "CASE1") (pin "32") (pinfunction "8_32") (pintype "passive"))
    )
    (net (code "77") (name "unconnected-(CASE1C-9-Pad33)") (class "Default")
      (node (ref "CASE1") (pin "33") (pinfunction "9_33") (pintype "passive"))
    )
    (net (code "78") (name "unconnected-(CASE1C-10-Pad34)") (class "Default")
      (node (ref "CASE1") (pin "34") (pinfunction "10_34") (pintype "passive"))
    )
    (net (code "79") (name "unconnected-(CASE1C-11-Pad35)") (class "Default")
      (node (ref "CASE1") (pin "35") (pinfunction "11_35") (pintype "passive"))
    )
    (net (code "80") (name "unconnected-(CASE1C-12-Pad36)") (class "Default")
      (node (ref "CASE1") (pin "36") (pinfunction "12_36") (pintype "passive"))
    )
    (net (code "81") (name "unconnected-(CASE1D-7-Pad43)") (class "Default")
      (node (ref "CASE1") (pin "43") (pinfunction "7_43") (pintype "passive"))
    )
    (net (code "82") (name "unconnected-(CASE1D-8-Pad44)") (class "Default")
      (node (ref "CASE1") (pin "44") (pinfunction "8_44") (pintype "passive"))
    )
    (net (code "83") (name "unconnected-(JP19-CTS-PadP$5)") (class "Default")
      (node (ref "JP19") (pin "P$5") (pinfunction "CTS_P$5") (pintype "bidirectional"))
    )
    (net (code "84") (name "unconnected-(JP19-DTR-PadP$1)") (class "Default")
      (node (ref "JP19") (pin "P$1") (pinfunction "DTR_P$1") (pintype "bidirectional"))
    )
    (net (code "85") (name "unconnected-(JP19-VCC-PadP$4)") (class "Default")
      (node (ref "JP19") (pin "P$4") (pinfunction "VCC_P$4") (pintype "bidirectional"))
    )
    (net (code "86") (name "unconnected-(U$2-AIO0-Pad30)") (class "Default")
      (node (ref "U$2") (pin "30") (pinfunction "AIO0_30") (pintype "bidirectional"))
    )
    (net (code "87") (name "unconnected-(U$2-AIO1-Pad35)") (class "Default")
      (node (ref "U$2") (pin "35") (pinfunction "AIO1_35") (pintype "bidirectional"))
    )
    (net (code "88") (name "unconnected-(U$2-PCMCLK-Pad7)") (class "Default")
      (node (ref "U$2") (pin "7") (pinfunction "PCMCLK_7") (pintype "bidirectional"))
    )
    (net (code "89") (name "unconnected-(U$2-PCMIN-Pad9)") (class "Default")
      (node (ref "U$2") (pin "9") (pinfunction "PCMIN_9") (pintype "bidirectional"))
    )
    (net (code "90") (name "unconnected-(U$2-PCMOUT-Pad10)") (class "Default")
      (node (ref "U$2") (pin "10") (pinfunction "PCMOUT_10") (pintype "bidirectional"))
    )
    (net (code "91") (name "unconnected-(U$2-PCMSYNC-Pad8)") (class "Default")
      (node (ref "U$2") (pin "8") (pinfunction "PCMSYNC_8") (pintype "bidirectional"))
    )
    (net (code "92") (name "unconnected-(U$2-PIO3-Pad20)") (class "Default")
      (node (ref "U$2") (pin "20") (pinfunction "PIO3_20") (pintype "bidirectional"))
    )
    (net (code "93") (name "unconnected-(U$2-PIO6-Pad3)") (class "Default")
      (node (ref "U$2") (pin "3") (pinfunction "PIO6_3") (pintype "bidirectional"))
    )
    (net (code "94") (name "unconnected-(U$2-PIO7-Pad4)") (class "Default")
      (node (ref "U$2") (pin "4") (pinfunction "PIO7_4") (pintype "bidirectional"))
    )
    (net (code "95") (name "unconnected-(U$2-PIO8-Pad31)") (class "Default")
      (node (ref "U$2") (pin "31") (pinfunction "PIO8_31") (pintype "bidirectional"))
    )
    (net (code "96") (name "unconnected-(U$2-PIO9-Pad32)") (class "Default")
      (node (ref "U$2") (pin "32") (pinfunction "PIO9_32") (pintype "bidirectional"))
    )
    (net (code "97") (name "unconnected-(U$2-PIO10-Pad33)") (class "Default")
      (node (ref "U$2") (pin "33") (pinfunction "PIO10_33") (pintype "bidirectional"))
    )
    (net (code "98") (name "unconnected-(U$2-PIO11-Pad34)") (class "Default")
      (node (ref "U$2") (pin "34") (pinfunction "PIO11_34") (pintype "bidirectional"))
    )
    (net (code "99") (name "unconnected-(U$2-RESET-Pad5)") (class "Default")
      (node (ref "U$2") (pin "5") (pinfunction "RESET_5") (pintype "bidirectional"))
    )
    (net (code "100") (name "unconnected-(U$2-SPICLK-Pad6)") (class "Default")
      (node (ref "U$2") (pin "6") (pinfunction "SPICLK_6") (pintype "bidirectional"))
    )
    (net (code "101") (name "unconnected-(U$2-SPICSB-Pad23)") (class "Default")
      (node (ref "U$2") (pin "23") (pinfunction "SPICSB_23") (pintype "bidirectional"))
    )
    (net (code "102") (name "unconnected-(U$2-SPIMISO-Pad24)") (class "Default")
      (node (ref "U$2") (pin "24") (pinfunction "SPIMISO_24") (pintype "bidirectional"))
    )
    (net (code "103") (name "unconnected-(U$2-SPIMOSI-Pad2)") (class "Default")
      (node (ref "U$2") (pin "2") (pinfunction "SPIMOSI_2") (pintype "bidirectional"))
    )
    (net (code "104") (name "unconnected-(U$2-UARTCTS-Pad16)") (class "Default")
      (node (ref "U$2") (pin "16") (pinfunction "UARTCTS_16") (pintype "bidirectional"))
    )
    (net (code "105") (name "unconnected-(U$2-UARTRTS-Pad15)") (class "Default")
      (node (ref "U$2") (pin "15") (pinfunction "UARTRTS_15") (pintype "bidirectional"))
    )
    (net (code "106") (name "unconnected-(U$2-USBD+-Pad17)") (class "Default")
      (node (ref "U$2") (pin "17") (pinfunction "USBD+_17") (pintype "bidirectional"))
    )
    (net (code "107") (name "unconnected-(U$2-USBD--Pad18)") (class "Default")
      (node (ref "U$2") (pin "18") (pinfunction "USBD-_18") (pintype "bidirectional"))
    )
    (net (code "108") (name "unconnected-(U7-CH-Pad11)") (class "Default")
      (node (ref "U7") (pin "11") (pinfunction "CH_11") (pintype "bidirectional"))
    )
    (net (code "109") (name "unconnected-(U8-RA4-Pad23)") (class "Default")
      (node (ref "U8") (pin "23") (pinfunction "RA4_23") (pintype "bidirectional"))
    )
    (net (code "110") (name "unconnected-(U8-RA6-Pad31)") (class "Default")
      (node (ref "U8") (pin "31") (pinfunction "RA6_31") (pintype "bidirectional"))
    )
    (net (code "111") (name "unconnected-(U8-RA7-Pad30)") (class "Default")
      (node (ref "U8") (pin "30") (pinfunction "RA7_30") (pintype "bidirectional"))
    )
    (net (code "112") (name "unconnected-(U8-RC0-Pad32)") (class "Default")
      (node (ref "U8") (pin "32") (pinfunction "RC0_32") (pintype "bidirectional"))
    )
    (net (code "113") (name "unconnected-(U8-RC1-Pad35)") (class "Default")
      (node (ref "U8") (pin "35") (pinfunction "RC1_35") (pintype "bidirectional"))
    )
    (net (code "114") (name "unconnected-(U8-RC2-Pad36)") (class "Default")
      (node (ref "U8") (pin "36") (pinfunction "RC2_36") (pintype "bidirectional"))
    )
    (net (code "115") (name "unconnected-(U8-RD0-Pad38)") (class "Default")
      (node (ref "U8") (pin "38") (pinfunction "RD0_38") (pintype "bidirectional"))
    )
    (net (code "116") (name "unconnected-(U8-RD2-Pad40)") (class "Default")
      (node (ref "U8") (pin "40") (pinfunction "RD2_40") (pintype "bidirectional"))
    )
    (net (code "117") (name "unconnected-(U8-RD3-Pad41)") (class "Default")
      (node (ref "U8") (pin "41") (pinfunction "RD3_41") (pintype "bidirectional"))
    )
    (net (code "118") (name "unconnected-(U8-RD4-Pad2)") (class "Default")
      (node (ref "U8") (pin "2") (pinfunction "RD4_2") (pintype "bidirectional"))
    )
  )
)
